# 10_-_Configuration_And_ADC.net
KiCad netlist of a schematic drawn in Altium Designer
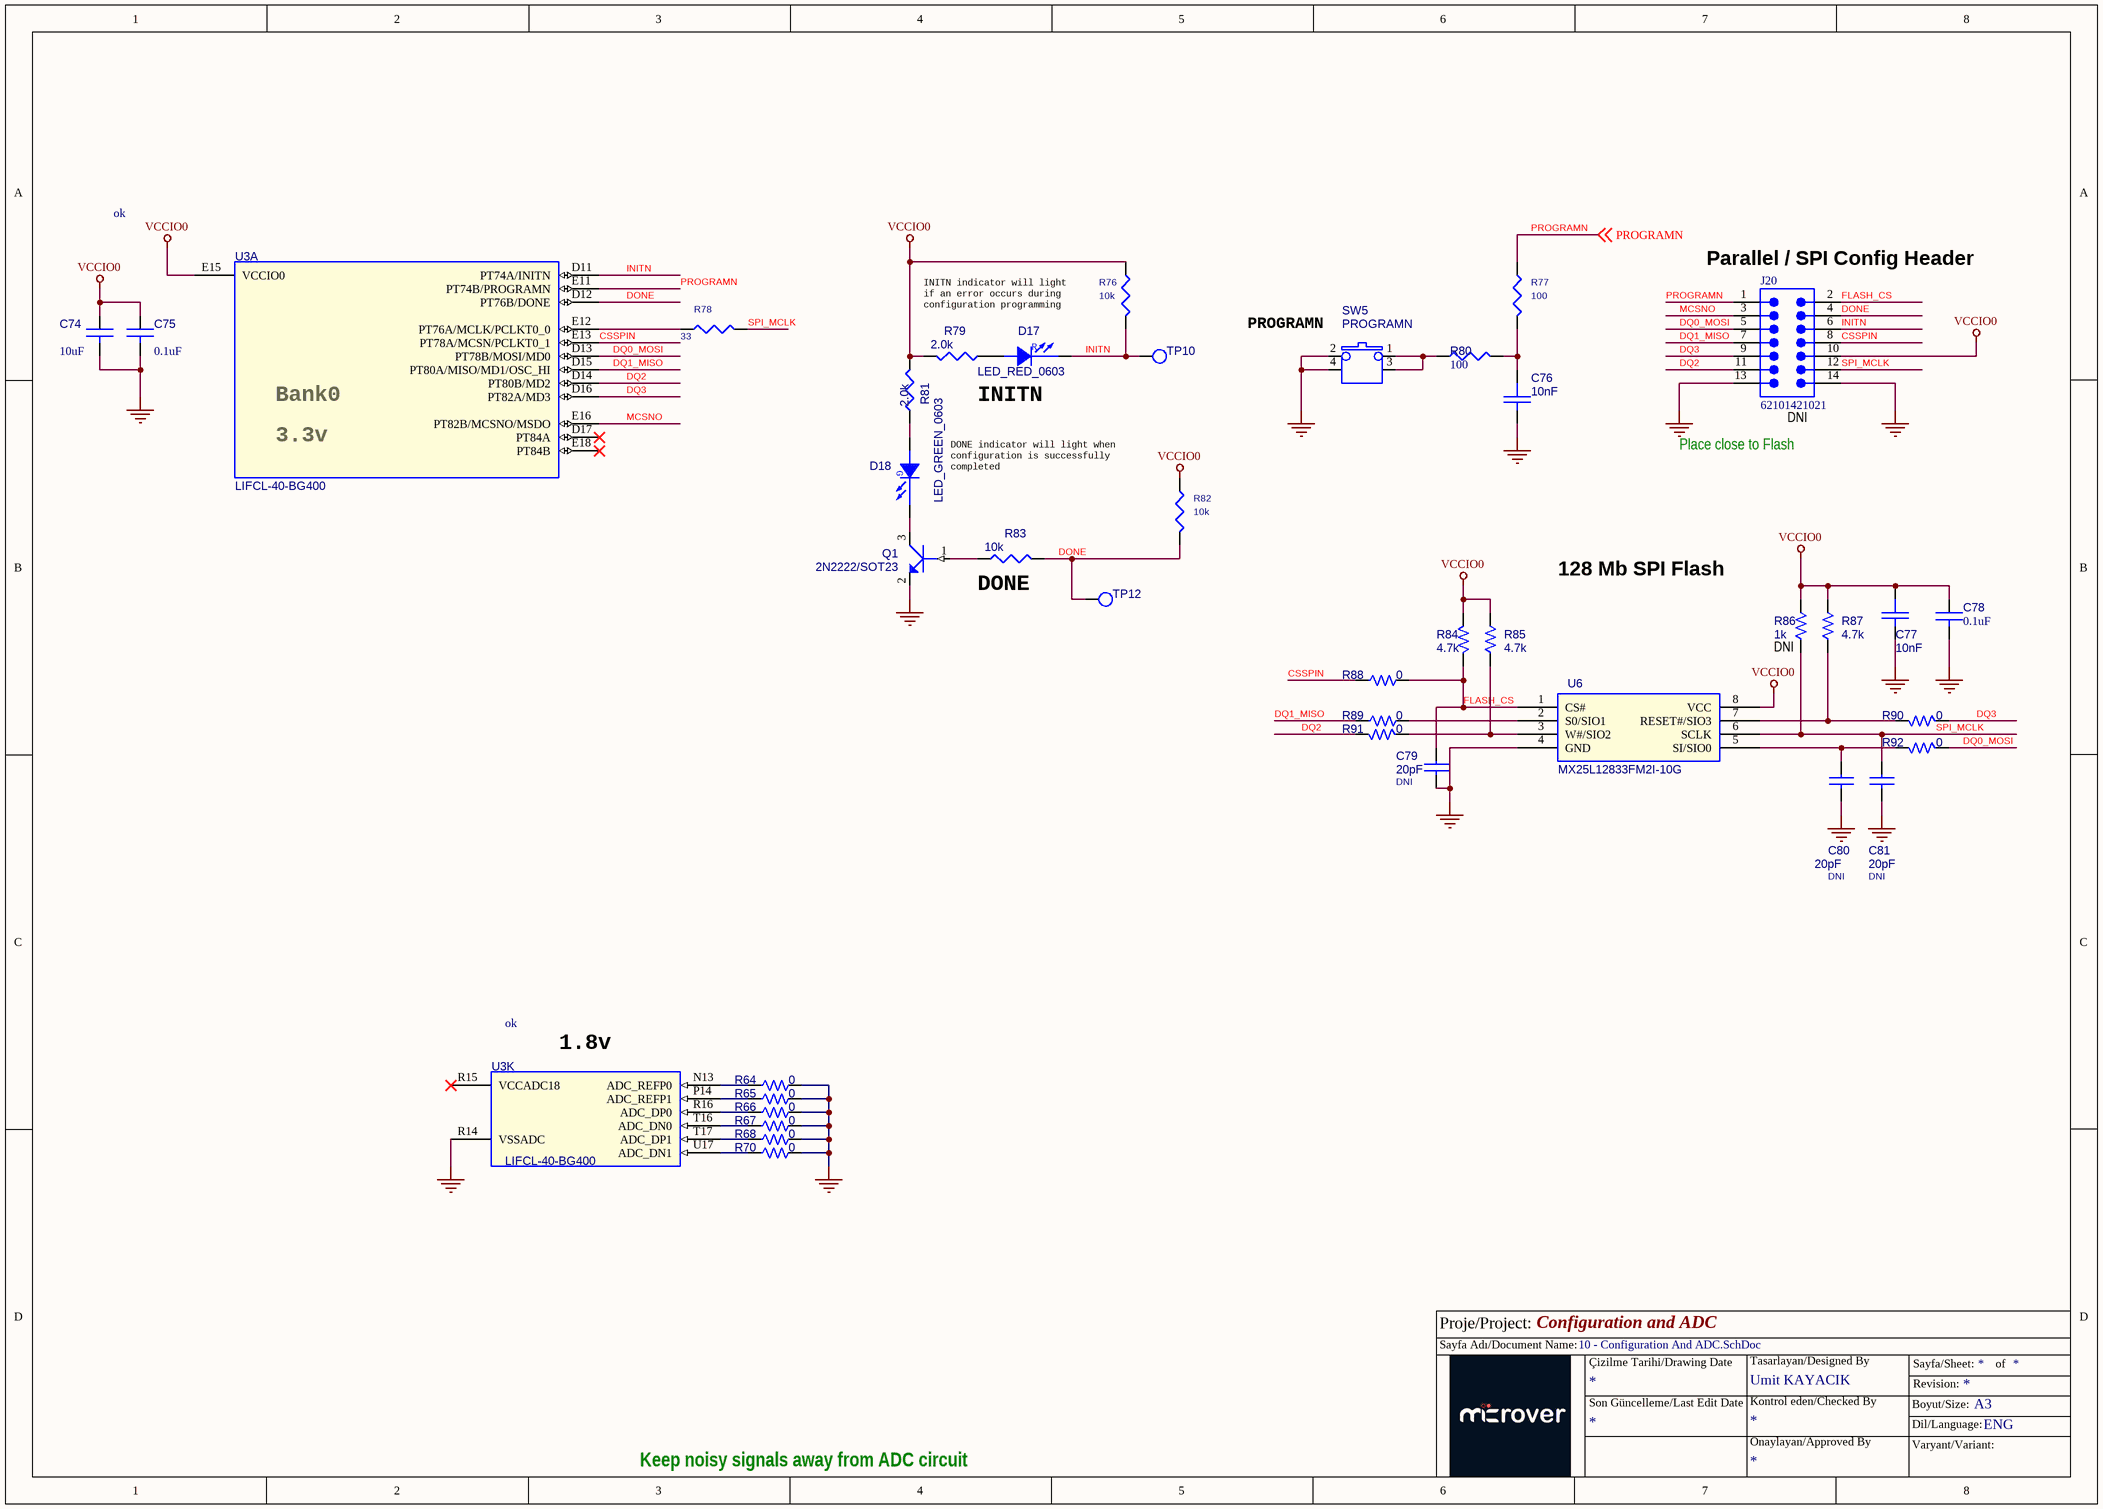
[diagram p0: 10 - Configuration And ADC.SchDoc]

(export (version "E")
  (design (tool "Eeschema 10.0.6"))
  (components
    (comp (ref "C74")
      (value "10uF")
      (footprint "C0603")
      (description "CAP CECAP CER 10UF 10V X5R 20% 0603")
      (fields
        (field (name "MANUFACTURER") "Taiyo Yuden")
        (field (name "MANUFACTURER PART NUMBER") "LMK107BJ106MALTD")
      )
      (libsource (lib "*") (part "10uF_0603"))
    )
    (comp (ref "C75")
      (value "0.1uF")
      (footprint "C0201")
      (description "CAP CER 0.1UF 25V 10% X5R 0201")
      (fields
        (field (name "MANUFACTURER") "Murata")
        (field (name "MANUFACTURER PART NUMBER") "GRM033R61E104KE14J")
      )
      (libsource (lib "*") (part "0u1_0402"))
    )
    (comp (ref "C76") (value "10nF") (footprint "RLP-130-A") (libsource (lib "*") (part "CAP_1")))
    (comp (ref "C77") (value "10nF") (footprint "RLP-130-A") (libsource (lib "*") (part "CAP_1")))
    (comp (ref "C78")
      (value "0.1uF")
      (footprint "C0402")
      (description "CAP CER 0.1UF 25V 10% X5R 0402")
      (fields
        (field (name "MANUFACTURER") "Murata")
        (field (name "MANUFACTURER PART NUMBER") "GRM033R61E104KE14J")
      )
      (libsource (lib "*") (part "0u1_0402"))
    )
    (comp (ref "C79")
      (value "20pF")
      (footprint "C0402")
      (fields (field (name "POPULATE") "DNI"))
      (libsource (lib "*") (part "CAP NP_Dup1"))
    )
    (comp (ref "C80")
      (value "20pF")
      (footprint "C0402")
      (fields (field (name "POPULATE") "DNI"))
      (libsource (lib "*") (part "CAP NP_Dup1"))
    )
    (comp (ref "C81")
      (value "20pF")
      (footprint "c0402")
      (fields (field (name "POPULATE") "DNI"))
      (libsource (lib "*") (part "CAP NP_Dup1"))
    )
    (comp (ref "D17")
      (value "LED_RED_0603")
      (footprint "APT1608")
      (libsource (lib "*") (part "LED-SMT1206_RED_0"))
    )
    (comp (ref "D18")
      (value "LED_GREEN_0603")
      (footprint "APT1608")
      (libsource (lib "*") (part "LED-SMT1206_GREEN_1"))
    )
    (comp (ref "J20")
      (value "62101421021")
      (footprint "62101421021")
      (description "Conn, Header, 14Pos, 2Row, 1.27Mm Rohs Compliant: Yes")
      (libsource (lib "Altium Content Vault") (part "Header_Male_2R_14P"))
    )
    (comp (ref "Q1") (value "2N2222/SOT23") (footprint "MMBT2222ALT-1") (libsource (lib "*") (part "2N2222")))
    (comp (ref "R64")
      (value "0")
      (footprint "R0201")
      (description "RES SMD 0.0OHM JUMPER 1/10W 0402")
      (fields (field (name "VOLTAGE") "RVMAX") (field (name "POWER") "RMAX"))
      (libsource (lib "*") (part "R_Dup2"))
    )
    (comp (ref "R65")
      (value "0")
      (footprint "R0201")
      (description "RES SMD 0.0OHM JUMPER 1/10W 0402")
      (fields (field (name "VOLTAGE") "RVMAX") (field (name "POWER") "RMAX"))
      (libsource (lib "*") (part "R_Dup2"))
    )
    (comp (ref "R66")
      (value "0")
      (footprint "R0201")
      (description "RES SMD 0.0OHM JUMPER 1/10W 0402")
      (fields (field (name "VOLTAGE") "RVMAX") (field (name "POWER") "RMAX"))
      (libsource (lib "*") (part "R_Dup2"))
    )
    (comp (ref "R67")
      (value "0")
      (footprint "R0201")
      (description "RES SMD 0.0OHM JUMPER 1/10W 0402")
      (fields (field (name "VOLTAGE") "RVMAX") (field (name "POWER") "RMAX"))
      (libsource (lib "*") (part "R_Dup2"))
    )
    (comp (ref "R68")
      (value "0")
      (footprint "R0201")
      (description "RES SMD 0.0OHM JUMPER 1/10W 0402")
      (fields (field (name "VOLTAGE") "RVMAX") (field (name "POWER") "RMAX"))
      (libsource (lib "*") (part "R_Dup2"))
    )
    (comp (ref "R70")
      (value "0")
      (footprint "R0201")
      (description "RES SMD 0.0OHM JUMPER 1/10W 0402")
      (fields (field (name "VOLTAGE") "RVMAX") (field (name "POWER") "RMAX"))
      (libsource (lib "*") (part "R_Dup2"))
    )
    (comp (ref "R76")
      (value "10k")
      (footprint "R0402")
      (description "RES SMD 10K OHM 1% 1/16W 0402")
      (fields (field (name "MANUFACTURER PART NUMBER") "RC0402FR-0710KL") (field (name "MFG") "Yageo"))
      (libsource (lib "*") (part "R_Dup3"))
    )
    (comp (ref "R77")
      (value "100")
      (footprint "R0402")
      (description "RES SMD 100 OHM 1% 1/16W 0402")
      (fields (field (name "MANUFACTURER PART NUMBER") "RC0402FR-07100RL") (field (name "MFG") "Yageo"))
      (libsource (lib "*") (part "R_Dup3"))
    )
    (comp (ref "R78")
      (value "33")
      (footprint "R0402")
      (description "RES SMD 33 OHM 1% 1/10W 0402")
      (fields
        (field (name "MANUFACTURER PART NUMBER") "ERJ-2RKF33R0X")
        (field (name "MANUFACTURER") "Panasonic")
      )
      (libsource (lib "*") (part "R_Dup3"))
    )
    (comp (ref "R79")
      (value "2.0k")
      (footprint "R0402")
      (description "RES SMD 1K OHM 1% 1/10W 0402")
      (fields
        (field (name "MANUFACTURER PART NUMBER") "ERJ-2RKF1001X")
        (field (name "MANUFACTURER") "Panasonic")
      )
      (libsource (lib "*") (part "RES_0"))
    )
    (comp (ref "R80")
      (value "100")
      (footprint "R0402")
      (description "RES SMD 100 OHM 1% 1/16W 0402")
      (fields
        (field (name "MANUFACTURER") "Yageo")
        (field (name "MANUFACTURER PART NUMBER") "RC0402FR-07100RL")
      )
      (libsource (lib "*") (part "0R_0603"))
    )
    (comp (ref "R81")
      (value "2.0k")
      (footprint "R0402")
      (description "RES SMD 1K OHM 1% 1/10W 0402")
      (fields
        (field (name "MANUFACTURER") "Panasonic")
        (field (name "MANUFACTURER PART NUMBER") "ERJ-2RKF1001X")
      )
      (libsource (lib "*") (part "RES_0"))
    )
    (comp (ref "R82")
      (value "10k")
      (footprint "R0402")
      (description "RES SMD 10K OHM 1% 1/16W 0402")
      (fields (field (name "MANUFACTURER PART NUMBER") "RC0402FR-0710KL") (field (name "MFG") "Yageo"))
      (libsource (lib "*") (part "R_Dup3"))
    )
    (comp (ref "R83")
      (value "10k")
      (footprint "R0402")
      (description "RES SMD 10K OHM 1% 1/16W 0402")
      (fields
        (field (name "MANUFACTURER") "Yageo")
        (field (name "MANUFACTURER PART NUMBER") "RC0402FR-0710KL")
      )
      (libsource (lib "*") (part "RES_0"))
    )
    (comp (ref "R84")
      (value "4.7k")
      (footprint "R0402")
      (description "RES SMD 4.7K OHM 5% 1/10W 0402")
      (fields (field (name "VOLTAGE") "RVMAX") (field (name "POWER") "RMAX"))
      (libsource (lib "*") (part "R_Dup2"))
    )
    (comp (ref "R85")
      (value "4.7k")
      (footprint "R0402")
      (description "RES SMD 4.7K OHM 5% 1/10W 0402")
      (fields (field (name "VOLTAGE") "RVMAX") (field (name "POWER") "RMAX"))
      (libsource (lib "*") (part "R_Dup2"))
    )
    (comp (ref "R86")
      (value "1k")
      (footprint "R0402")
      (description "RES SMD 1K OHM 1% 1/10W 0402")
      (fields (field (name "VOLTAGE") "RVMAX") (field (name "POWER") "RMAX"))
      (libsource (lib "*") (part "R_Dup2"))
    )
    (comp (ref "R87")
      (value "4.7k")
      (footprint "R0402")
      (description "RES SMD 4.7K OHM 5% 1/10W 0402")
      (fields (field (name "VOLTAGE") "RVMAX") (field (name "POWER") "RMAX"))
      (libsource (lib "*") (part "R_Dup2"))
    )
    (comp (ref "R88")
      (value "0")
      (footprint "R0402")
      (description "RES SMD 0.0OHM JUMPER 1/10W 0402")
      (fields (field (name "VOLTAGE") "RVMAX") (field (name "POWER") "RMAX"))
      (libsource (lib "*") (part "R_Dup2"))
    )
    (comp (ref "R89")
      (value "0")
      (footprint "R0402")
      (description "RES SMD 0.0OHM JUMPER 1/10W 0402")
      (fields (field (name "VOLTAGE") "RVMAX") (field (name "POWER") "RMAX"))
      (libsource (lib "*") (part "R_Dup2"))
    )
    (comp (ref "R90")
      (value "0")
      (footprint "R0402")
      (description "RES SMD 0.0OHM JUMPER 1/10W 0402")
      (fields (field (name "VOLTAGE") "RVMAX") (field (name "POWER") "RMAX"))
      (libsource (lib "*") (part "R_Dup2"))
    )
    (comp (ref "R91")
      (value "0")
      (footprint "R0402")
      (description "RES SMD 0.0OHM JUMPER 1/10W 0402")
      (fields (field (name "VOLTAGE") "RVMAX") (field (name "POWER") "RMAX"))
      (libsource (lib "*") (part "R_Dup2"))
    )
    (comp (ref "R92")
      (value "0")
      (footprint "R0402")
      (description "RES SMD 0.0OHM JUMPER 1/10W 0402")
      (fields (field (name "VOLTAGE") "RVMAX") (field (name "POWER") "RMAX"))
      (libsource (lib "*") (part "R_Dup2"))
    )
    (comp (ref "SW5")
      (value "PROGRAMN")
      (footprint "4psmd_switch")
      (description "SWITCH TACTILE SPST-NO 0.05A 12V")
      (fields (field (name "MANUFACTURER PART NUMBER") "434153017835") (field (name "MFG") "Wurth"))
      (libsource (lib "*") (part "SW PUSHBUTTON-SPST/SM"))
    )
    (comp (ref "TP10") (value "TestPoint") (footprint "TP_1MM") (libsource (lib "*") (part "T POINT R")))
    (comp (ref "TP12") (value "TestPoint") (footprint "TP_1MM") (libsource (lib "*") (part "T POINT R")))
    (comp (ref "U3")
      (value "LIFCL-40-BG400")
      (footprint "LIFCL-40-BG400")
      (libsource (lib "*") (part "LIFCL-40-BG400"))
    )
    (comp (ref "U6")
      (value "MX25L12833FM2I-10G")
      (footprint "SO8_MX25L12833FM2I10G")
      (description "IC FLASH 128MBIT 104MHZ 8SOP")
      (fields (field (name "MANUFACTURER") "Macronix"))
      (libsource (lib "*") (part "N25QxxxA13xF8_0"))
    )
  )
  (nets
    (net (code "1") (name "/CSSPIN") (class "Default")
      (node (ref "J20") (pin "8") (pinfunction "8_8") (pintype "passive"))
      (node (ref "R88") (pin "1") (pinfunction "1_1") (pintype "passive"))
      (node (ref "U3") (pin "E13") (pinfunction "PT78A/MCSN/PCLKT0_1_E13") (pintype "bidirectional"))
    )
    (net (code "2") (name "/DONE") (class "Default")
      (node (ref "J20") (pin "4") (pinfunction "4_4") (pintype "passive"))
      (node (ref "R82") (pin "2") (pinfunction "2_2") (pintype "passive"))
      (node (ref "R83") (pin "2") (pinfunction "2_2") (pintype "passive"))
      (node (ref "TP12") (pin "1") (pinfunction "TP_1") (pintype "passive"))
      (node (ref "U3") (pin "D12") (pinfunction "PT76B/DONE_D12") (pintype "bidirectional"))
    )
    (net (code "3") (name "/DQ0_MOSI") (class "Default")
      (node (ref "J20") (pin "5") (pinfunction "5_5") (pintype "passive"))
      (node (ref "R92") (pin "1") (pinfunction "1_1") (pintype "passive"))
      (node (ref "U3") (pin "D13") (pinfunction "PT78B/MOSI/MD0_D13") (pintype "bidirectional"))
    )
    (net (code "4") (name "/DQ1_MISO") (class "Default")
      (node (ref "J20") (pin "7") (pinfunction "7_7") (pintype "passive"))
      (node (ref "R89") (pin "1") (pinfunction "1_1") (pintype "passive"))
      (node (ref "U3") (pin "D15") (pinfunction "PT80A/MISO/MD1/OSC_HI_D15") (pintype "bidirectional"))
    )
    (net (code "5") (name "/DQ2") (class "Default")
      (node (ref "J20") (pin "11") (pinfunction "11_11") (pintype "passive"))
      (node (ref "R91") (pin "2") (pinfunction "2_2") (pintype "passive"))
      (node (ref "U3") (pin "D14") (pinfunction "PT80B/MD2_D14") (pintype "bidirectional"))
    )
    (net (code "6") (name "/DQ3") (class "Default")
      (node (ref "J20") (pin "9") (pinfunction "9_9") (pintype "passive"))
      (node (ref "R90") (pin "1") (pinfunction "1_1") (pintype "passive"))
      (node (ref "U3") (pin "D16") (pinfunction "PT82A/MD3_D16") (pintype "bidirectional"))
    )
    (net (code "7") (name "/FLASH_CS") (class "Default")
      (node (ref "C79") (pin "1") (pinfunction "1_1") (pintype "passive"))
      (node (ref "J20") (pin "2") (pinfunction "2_2") (pintype "passive"))
      (node (ref "R84") (pin "1") (pinfunction "1_1") (pintype "passive"))
      (node (ref "R88") (pin "2") (pinfunction "2_2") (pintype "passive"))
      (node (ref "U6") (pin "1") (pinfunction "CS#_1") (pintype "passive"))
    )
    (net (code "8") (name "/INITN") (class "Default")
      (node (ref "D17") (pin "1") (pinfunction "CATHODE_1") (pintype "passive"))
      (node (ref "J20") (pin "6") (pinfunction "6_6") (pintype "passive"))
      (node (ref "R76") (pin "2") (pinfunction "2_2") (pintype "passive"))
      (node (ref "TP10") (pin "1") (pinfunction "TP_1") (pintype "passive"))
      (node (ref "U3") (pin "D11") (pinfunction "PT74A/INITN_D11") (pintype "bidirectional"))
    )
    (net (code "9") (name "/MCSNO") (class "Default")
      (node (ref "J20") (pin "3") (pinfunction "3_3") (pintype "passive"))
      (node (ref "U3") (pin "E16") (pinfunction "PT82B/MCSNO/MSDO_E16") (pintype "bidirectional"))
    )
    (net (code "10") (name "/SPI_MCLK") (class "Default")
      (node (ref "C81") (pin "1") (pinfunction "1_1") (pintype "passive"))
      (node (ref "J20") (pin "12") (pinfunction "12_12") (pintype "passive"))
      (node (ref "R78") (pin "1") (pinfunction "1_1") (pintype "passive"))
      (node (ref "R86") (pin "1") (pinfunction "1_1") (pintype "passive"))
      (node (ref "U6") (pin "6") (pinfunction "SCLK_6") (pintype "passive"))
    )
    (net (code "11") (name "GND") (class "Default")
      (node (ref "C74") (pin "2") (pinfunction "2_2") (pintype "passive"))
      (node (ref "C75") (pin "2") (pinfunction "2_2") (pintype "passive"))
      (node (ref "C76") (pin "2") (pinfunction "2_2") (pintype "passive"))
      (node (ref "C77") (pin "2") (pinfunction "2_2") (pintype "passive"))
      (node (ref "C78") (pin "2") (pinfunction "2_2") (pintype "passive"))
      (node (ref "C79") (pin "2") (pinfunction "2_2") (pintype "passive"))
      (node (ref "C80") (pin "2") (pinfunction "2_2") (pintype "passive"))
      (node (ref "C81") (pin "2") (pinfunction "2_2") (pintype "passive"))
      (node (ref "J20") (pin "13") (pinfunction "13_13") (pintype "passive"))
      (node (ref "J20") (pin "14") (pinfunction "14_14") (pintype "passive"))
      (node (ref "Q1") (pin "2") (pinfunction "EMITTER_2") (pintype "passive"))
      (node (ref "R64") (pin "2") (pinfunction "2_2") (pintype "passive"))
      (node (ref "R65") (pin "2") (pinfunction "2_2") (pintype "passive"))
      (node (ref "R66") (pin "2") (pinfunction "2_2") (pintype "passive"))
      (node (ref "R67") (pin "2") (pinfunction "2_2") (pintype "passive"))
      (node (ref "R68") (pin "2") (pinfunction "2_2") (pintype "passive"))
      (node (ref "R70") (pin "2") (pinfunction "2_2") (pintype "passive"))
      (node (ref "SW5") (pin "2") (pinfunction "2_2") (pintype "passive"))
      (node (ref "SW5") (pin "4") (pinfunction "4_4") (pintype "passive"))
      (node (ref "U3") (pin "R14") (pinfunction "VSSADC_R14") (pintype "power_in"))
      (node (ref "U6") (pin "4") (pinfunction "GND_4") (pintype "power_in"))
    )
    (net (code "12") (name "Net-(C76-Pad1)") (class "Default")
      (node (ref "C76") (pin "1") (pinfunction "1_1") (pintype "passive"))
      (node (ref "R77") (pin "2") (pinfunction "2_2") (pintype "passive"))
      (node (ref "R80") (pin "2") (pinfunction "2_2") (pintype "passive"))
    )
    (net (code "13") (name "Net-(D17-ANODE)") (class "Default")
      (node (ref "D17") (pin "2") (pinfunction "ANODE_2") (pintype "passive"))
      (node (ref "R79") (pin "1") (pinfunction "1_1") (pintype "passive"))
    )
    (net (code "14") (name "Net-(D18-ANODE)") (class "Default")
      (node (ref "D18") (pin "2") (pinfunction "ANODE_2") (pintype "passive"))
      (node (ref "R81") (pin "1") (pinfunction "1_1") (pintype "passive"))
    )
    (net (code "15") (name "Net-(D18-CATHODE)") (class "Default")
      (node (ref "D18") (pin "1") (pinfunction "CATHODE_1") (pintype "passive"))
      (node (ref "Q1") (pin "3") (pinfunction "COLLECTOR_3") (pintype "passive"))
    )
    (net (code "16") (name "Net-(Q1-BASE)") (class "Default")
      (node (ref "Q1") (pin "1") (pinfunction "BASE_1") (pintype "input"))
      (node (ref "R83") (pin "1") (pinfunction "1_1") (pintype "passive"))
    )
    (net (code "17") (name "Net-(R80-Pad1)") (class "Default")
      (node (ref "R80") (pin "1") (pinfunction "1_1") (pintype "passive"))
      (node (ref "SW5") (pin "1") (pinfunction "1_1") (pintype "passive"))
      (node (ref "SW5") (pin "3") (pinfunction "3_3") (pintype "passive"))
    )
    (net (code "18") (name "Net-(U3A-PT76A{slash}MCLK{slash}PCLKT0_0)") (class "Default")
      (node (ref "R78") (pin "2") (pinfunction "2_2") (pintype "passive"))
      (node (ref "U3") (pin "E12") (pinfunction "PT76A/MCLK/PCLKT0_0_E12") (pintype "bidirectional"))
    )
    (net (code "19") (name "Net-(U3K-ADC_DN0)") (class "Default")
      (node (ref "R67") (pin "1") (pinfunction "1_1") (pintype "passive"))
      (node (ref "U3") (pin "T16") (pinfunction "ADC_DN0_T16") (pintype "input"))
    )
    (net (code "20") (name "Net-(U3K-ADC_DN1)") (class "Default")
      (node (ref "R70") (pin "1") (pinfunction "1_1") (pintype "passive"))
      (node (ref "U3") (pin "U17") (pinfunction "ADC_DN1_U17") (pintype "input"))
    )
    (net (code "21") (name "Net-(U3K-ADC_DP0)") (class "Default")
      (node (ref "R66") (pin "1") (pinfunction "1_1") (pintype "passive"))
      (node (ref "U3") (pin "R16") (pinfunction "ADC_DP0_R16") (pintype "input"))
    )
    (net (code "22") (name "Net-(U3K-ADC_DP1)") (class "Default")
      (node (ref "R68") (pin "1") (pinfunction "1_1") (pintype "passive"))
      (node (ref "U3") (pin "T17") (pinfunction "ADC_DP1_T17") (pintype "input"))
    )
    (net (code "23") (name "Net-(U3K-ADC_REFP0)") (class "Default")
      (node (ref "R64") (pin "1") (pinfunction "1_1") (pintype "passive"))
      (node (ref "U3") (pin "N13") (pinfunction "ADC_REFP0_N13") (pintype "input"))
    )
    (net (code "24") (name "Net-(U3K-ADC_REFP1)") (class "Default")
      (node (ref "R65") (pin "1") (pinfunction "1_1") (pintype "passive"))
      (node (ref "U3") (pin "P14") (pinfunction "ADC_REFP1_P14") (pintype "input"))
    )
    (net (code "25") (name "Net-(U6-RESET#{slash}SIO3)") (class "Default")
      (node (ref "R87") (pin "1") (pinfunction "1_1") (pintype "passive"))
      (node (ref "R90") (pin "2") (pinfunction "2_2") (pintype "passive"))
      (node (ref "U6") (pin "7") (pinfunction "RESET#/SIO3_7") (pintype "passive"))
    )
    (net (code "26") (name "Net-(U6-S0{slash}SIO1)") (class "Default")
      (node (ref "R89") (pin "2") (pinfunction "2_2") (pintype "passive"))
      (node (ref "U6") (pin "2") (pinfunction "S0/SIO1_2") (pintype "passive"))
    )
    (net (code "27") (name "Net-(U6-SI{slash}SIO0)") (class "Default")
      (node (ref "C80") (pin "1") (pinfunction "1_1") (pintype "passive"))
      (node (ref "R92") (pin "2") (pinfunction "2_2") (pintype "passive"))
      (node (ref "U6") (pin "5") (pinfunction "SI/SIO0_5") (pintype "passive"))
    )
    (net (code "28") (name "Net-(U6-W#{slash}SIO2)") (class "Default")
      (node (ref "R85") (pin "1") (pinfunction "1_1") (pintype "passive"))
      (node (ref "R91") (pin "1") (pinfunction "1_1") (pintype "passive"))
      (node (ref "U6") (pin "3") (pinfunction "W#/SIO2_3") (pintype "passive"))
    )
    (net (code "29") (name "PROGRAMN") (class "Default")
      (node (ref "J20") (pin "1") (pinfunction "1_1") (pintype "passive"))
      (node (ref "R77") (pin "1") (pinfunction "1_1") (pintype "passive"))
      (node (ref "U3") (pin "E11") (pinfunction "PT74B/PROGRAMN_E11") (pintype "bidirectional"))
    )
    (net (code "30") (name "VCCIO0") (class "Default")
      (node (ref "C74") (pin "1") (pinfunction "1_1") (pintype "passive"))
      (node (ref "C75") (pin "1") (pinfunction "1_1") (pintype "passive"))
      (node (ref "C77") (pin "1") (pinfunction "1_1") (pintype "passive"))
      (node (ref "C78") (pin "1") (pinfunction "1_1") (pintype "passive"))
      (node (ref "J20") (pin "10") (pinfunction "10_10") (pintype "passive"))
      (node (ref "R76") (pin "1") (pinfunction "1_1") (pintype "passive"))
      (node (ref "R79") (pin "2") (pinfunction "2_2") (pintype "passive"))
      (node (ref "R81") (pin "2") (pinfunction "2_2") (pintype "passive"))
      (node (ref "R82") (pin "1") (pinfunction "1_1") (pintype "passive"))
      (node (ref "R84") (pin "2") (pinfunction "2_2") (pintype "passive"))
      (node (ref "R85") (pin "2") (pinfunction "2_2") (pintype "passive"))
      (node (ref "R86") (pin "2") (pinfunction "2_2") (pintype "passive"))
      (node (ref "R87") (pin "2") (pinfunction "2_2") (pintype "passive"))
      (node (ref "U3") (pin "E15") (pinfunction "VCCIO0_E15") (pintype "power_in"))
      (node (ref "U6") (pin "8") (pinfunction "VCC_8") (pintype "power_in"))
    )
    (net (code "31") (name "unconnected-(U3A-PT84A-PadD17)") (class "Default")
      (node (ref "U3") (pin "D17") (pinfunction "PT84A_D17") (pintype "bidirectional+no_connect"))
    )
    (net (code "32") (name "unconnected-(U3A-PT84B-PadE18)") (class "Default")
      (node (ref "U3") (pin "E18") (pinfunction "PT84B_E18") (pintype "bidirectional+no_connect"))
    )
    (net (code "33") (name "unconnected-(U3K-VCCADC18-PadR15)") (class "Default")
      (node (ref "U3") (pin "R15") (pinfunction "VCCADC18_R15") (pintype "power_in+no_connect"))
    )
  )
)
